# SENSOR_SCH_FPC.net
KiCad netlist of a schematic drawn in EasyEDA
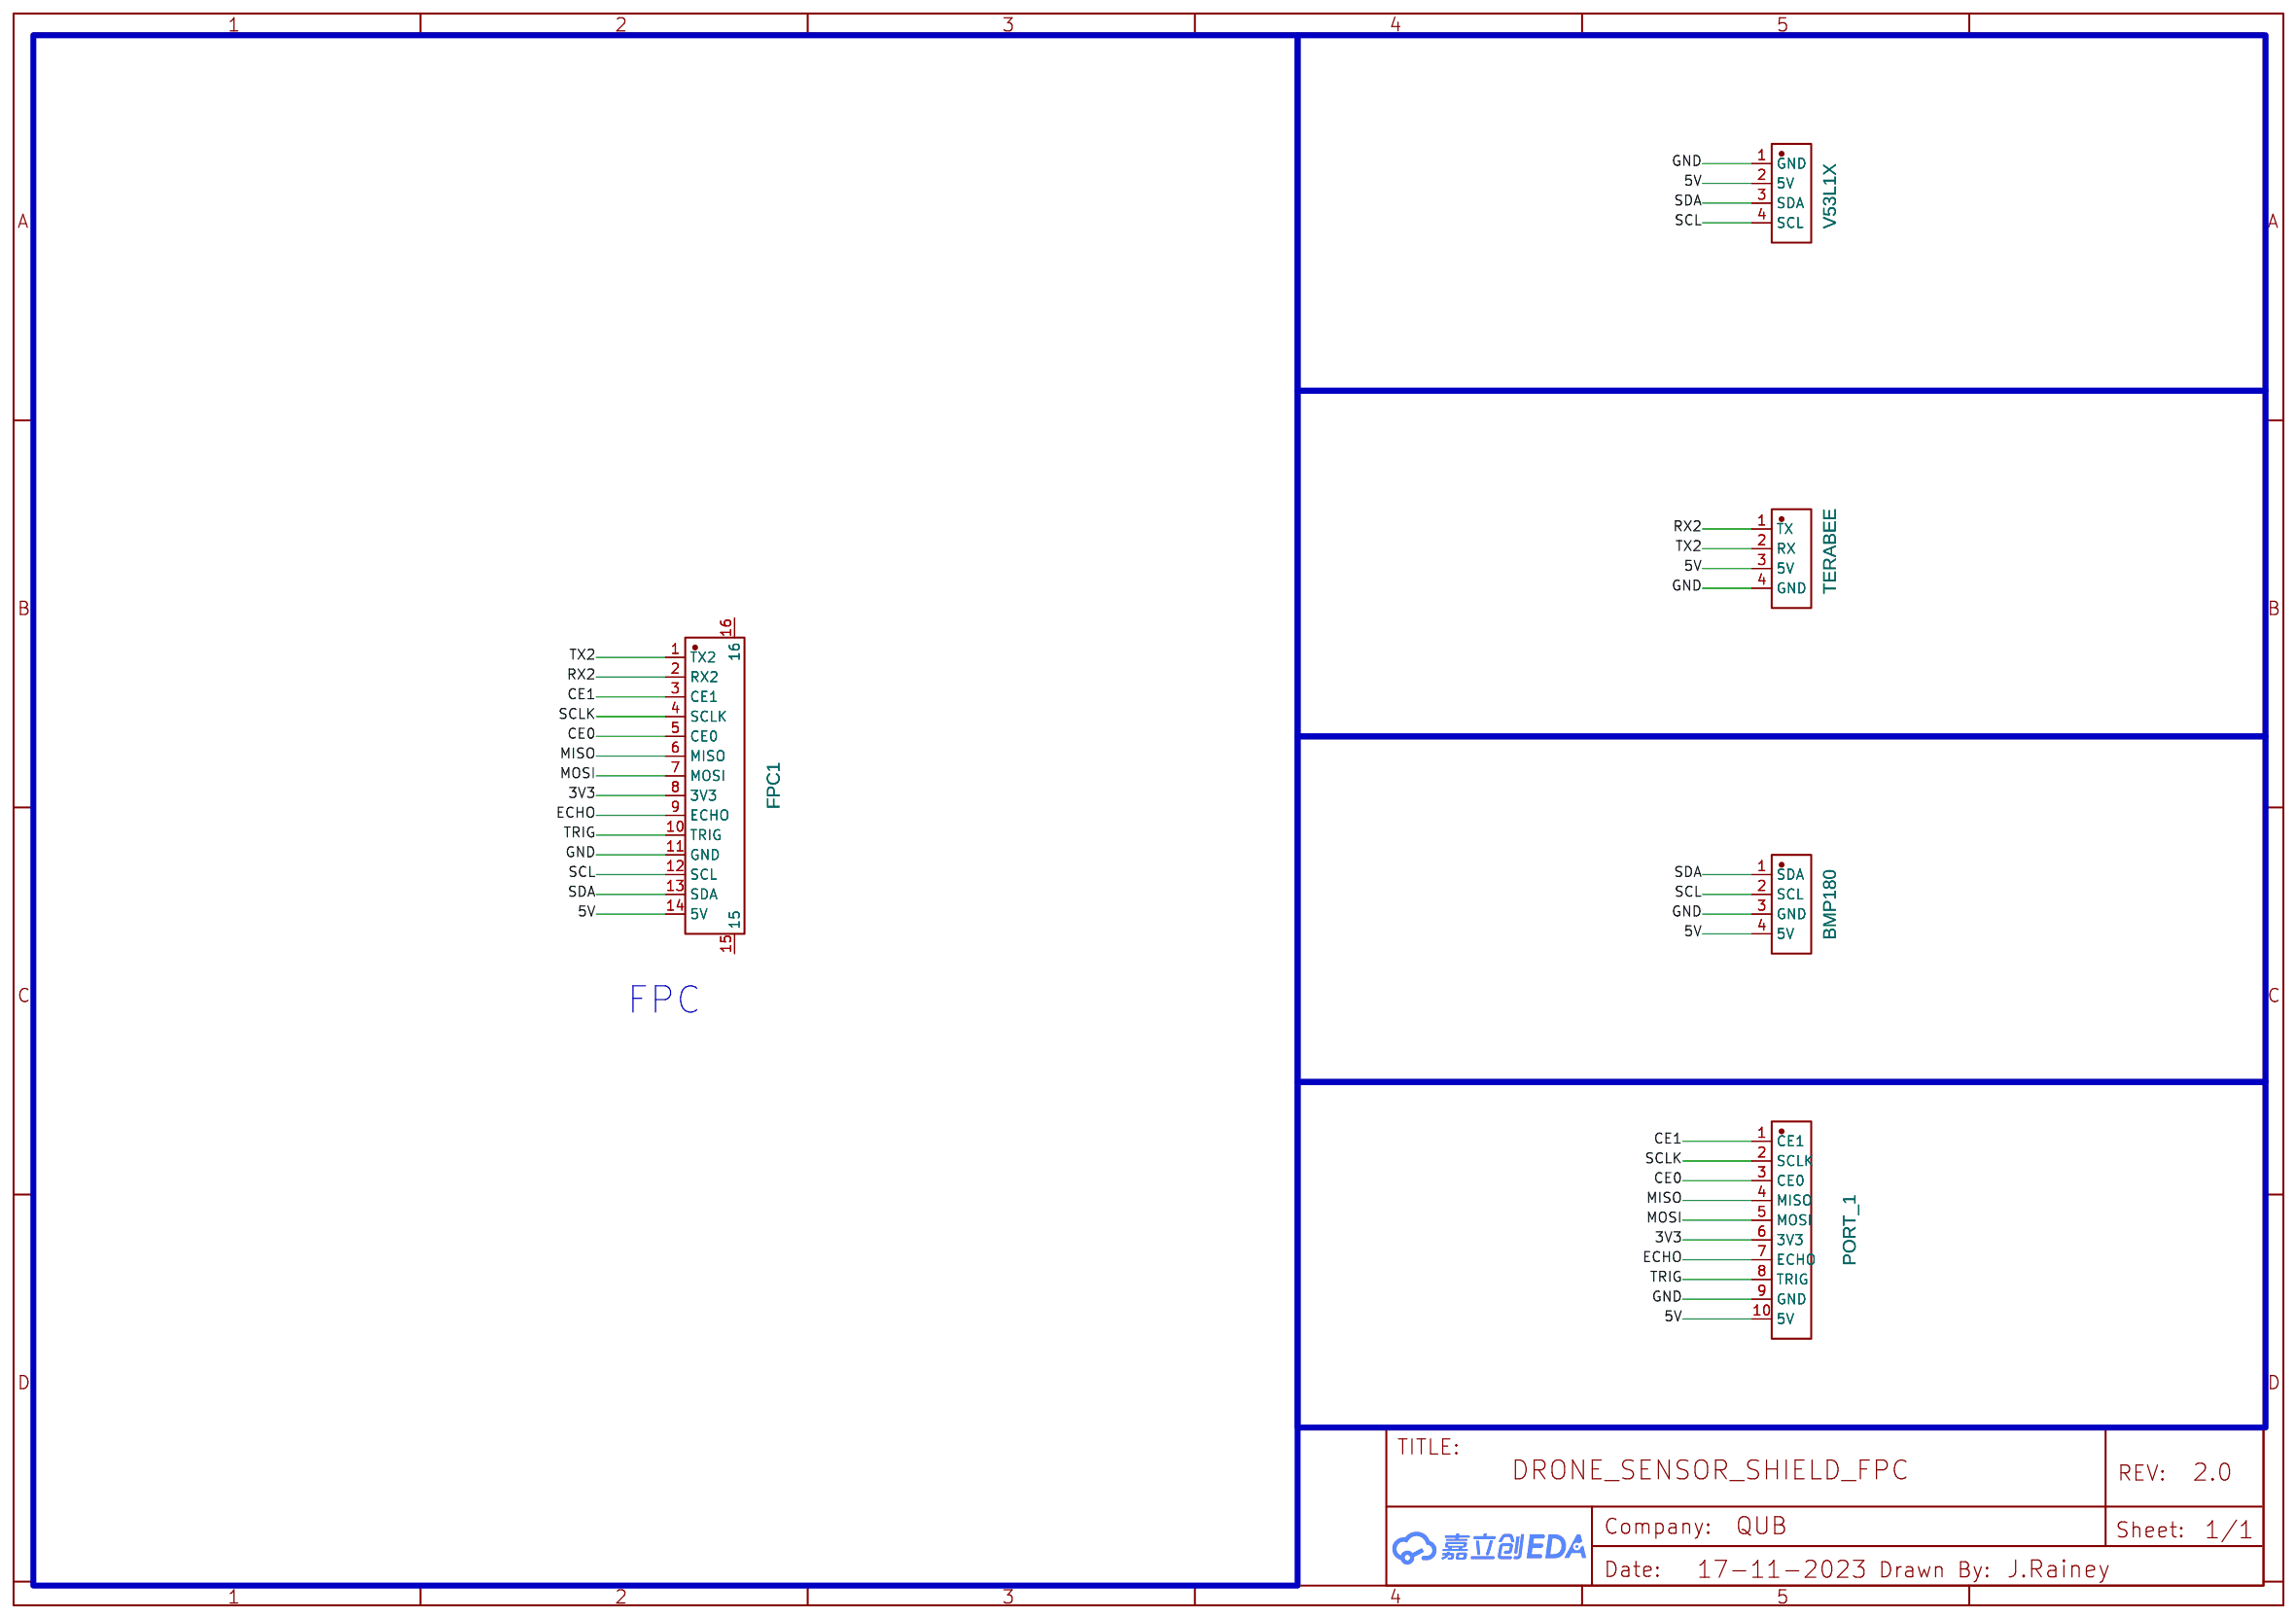
[diagram p0: schematic sheet]

(export (version "E")
  (design (tool "Eeschema 10.0.6"))
  (components
    (comp (ref "BMP180")
      (value "PZ254V-11-04P")
      (fields (field (name "BOM_Supplier Part") "C492403"))
      (libsource (lib "") (part "PZ254V-11-04P_2"))
    )
    (comp (ref "FPC1")
      (value "1.0K-FX-14PWB")
      (fields (field (name "Manufacturer") "HDGC(华德共创)"))
      (libsource (lib "") (part "1.0K-FX-14PWB"))
    )
    (comp (ref "PORT_1")
      (value "PORT_1")
      (fields (field (name "Manufacturer Part") "cn10_2r54_10x1"))
      (libsource (lib "") (part "CN10_2R54_10X1"))
    )
    (comp (ref "TERABEE")
      (value "PZ254V-11-04P")
      (fields (field (name "BOM_Supplier Part") "C492403"))
      (libsource (lib "") (part "PZ254V-11-04P"))
    )
    (comp (ref "V53L1X")
      (value "PZ254V-11-04P")
      (fields (field (name "BOM_Supplier Part") "C492403"))
      (libsource (lib "") (part "PZ254V-11-04P_1"))
    )
  )
  (nets
    (net (code "1") (name "/3V3") (class "Default")
      (node (ref "FPC1") (pin "8") (pinfunction "3V3_8") (pintype "unspecified"))
      (node (ref "PORT_1") (pin "6") (pinfunction "3V3_6") (pintype "unspecified"))
    )
    (net (code "2") (name "/5V") (class "Default")
      (node (ref "BMP180") (pin "4") (pinfunction "5V_4") (pintype "unspecified"))
      (node (ref "FPC1") (pin "14") (pinfunction "5V_14") (pintype "unspecified"))
      (node (ref "PORT_1") (pin "10") (pinfunction "5V_10") (pintype "unspecified"))
      (node (ref "TERABEE") (pin "3") (pinfunction "5V_3") (pintype "unspecified"))
      (node (ref "V53L1X") (pin "2") (pinfunction "5V_2") (pintype "unspecified"))
    )
    (net (code "3") (name "/CE0") (class "Default")
      (node (ref "FPC1") (pin "5") (pinfunction "CE0_5") (pintype "unspecified"))
      (node (ref "PORT_1") (pin "3") (pinfunction "CE0_3") (pintype "unspecified"))
    )
    (net (code "4") (name "/CE1") (class "Default")
      (node (ref "FPC1") (pin "3") (pinfunction "CE1_3") (pintype "unspecified"))
      (node (ref "PORT_1") (pin "1") (pinfunction "CE1_1") (pintype "unspecified"))
    )
    (net (code "5") (name "/ECHO") (class "Default")
      (node (ref "FPC1") (pin "9") (pinfunction "ECHO_9") (pintype "unspecified"))
      (node (ref "PORT_1") (pin "7") (pinfunction "ECHO_7") (pintype "unspecified"))
    )
    (net (code "6") (name "/GND") (class "Default")
      (node (ref "BMP180") (pin "3") (pinfunction "GND_3") (pintype "unspecified"))
      (node (ref "FPC1") (pin "11") (pinfunction "GND_11") (pintype "unspecified"))
      (node (ref "PORT_1") (pin "9") (pinfunction "GND_9") (pintype "unspecified"))
      (node (ref "TERABEE") (pin "4") (pinfunction "GND_4") (pintype "unspecified"))
      (node (ref "V53L1X") (pin "1") (pinfunction "GND_1") (pintype "unspecified"))
    )
    (net (code "7") (name "/MISO") (class "Default")
      (node (ref "FPC1") (pin "6") (pinfunction "MISO_6") (pintype "unspecified"))
      (node (ref "PORT_1") (pin "4") (pinfunction "MISO_4") (pintype "unspecified"))
    )
    (net (code "8") (name "/MOSI") (class "Default")
      (node (ref "FPC1") (pin "7") (pinfunction "MOSI_7") (pintype "unspecified"))
      (node (ref "PORT_1") (pin "5") (pinfunction "MOSI_5") (pintype "unspecified"))
    )
    (net (code "9") (name "/RX2") (class "Default")
      (node (ref "FPC1") (pin "2") (pinfunction "RX2_2") (pintype "unspecified"))
      (node (ref "TERABEE") (pin "1") (pinfunction "TX_1") (pintype "unspecified"))
    )
    (net (code "10") (name "/SCL") (class "Default")
      (node (ref "BMP180") (pin "2") (pinfunction "SCL_2") (pintype "unspecified"))
      (node (ref "FPC1") (pin "12") (pinfunction "SCL_12") (pintype "unspecified"))
      (node (ref "V53L1X") (pin "4") (pinfunction "SCL_4") (pintype "unspecified"))
    )
    (net (code "11") (name "/SCLK") (class "Default")
      (node (ref "FPC1") (pin "4") (pinfunction "SCLK_4") (pintype "unspecified"))
      (node (ref "PORT_1") (pin "2") (pinfunction "SCLK_2") (pintype "unspecified"))
    )
    (net (code "12") (name "/SDA") (class "Default")
      (node (ref "BMP180") (pin "1") (pinfunction "SDA_1") (pintype "unspecified"))
      (node (ref "FPC1") (pin "13") (pinfunction "SDA_13") (pintype "unspecified"))
      (node (ref "V53L1X") (pin "3") (pinfunction "SDA_3") (pintype "unspecified"))
    )
    (net (code "13") (name "/TRIG") (class "Default")
      (node (ref "FPC1") (pin "10") (pinfunction "TRIG_10") (pintype "unspecified"))
      (node (ref "PORT_1") (pin "8") (pinfunction "TRIG_8") (pintype "unspecified"))
    )
    (net (code "14") (name "/TX2") (class "Default")
      (node (ref "FPC1") (pin "1") (pinfunction "TX2_1") (pintype "unspecified"))
      (node (ref "TERABEE") (pin "2") (pinfunction "RX_2") (pintype "unspecified"))
    )
    (net (code "15") (name "unconnected-(FPC1-Pad15)") (class "Default")
      (node (ref "FPC1") (pin "15") (pinfunction "15_15") (pintype "unspecified"))
    )
    (net (code "16") (name "unconnected-(FPC1-Pad16)") (class "Default")
      (node (ref "FPC1") (pin "16") (pinfunction "16_16") (pintype "unspecified"))
    )
  )
)
